# 4_TTL.net
KiCad netlist of a schematic drawn in EAGLE
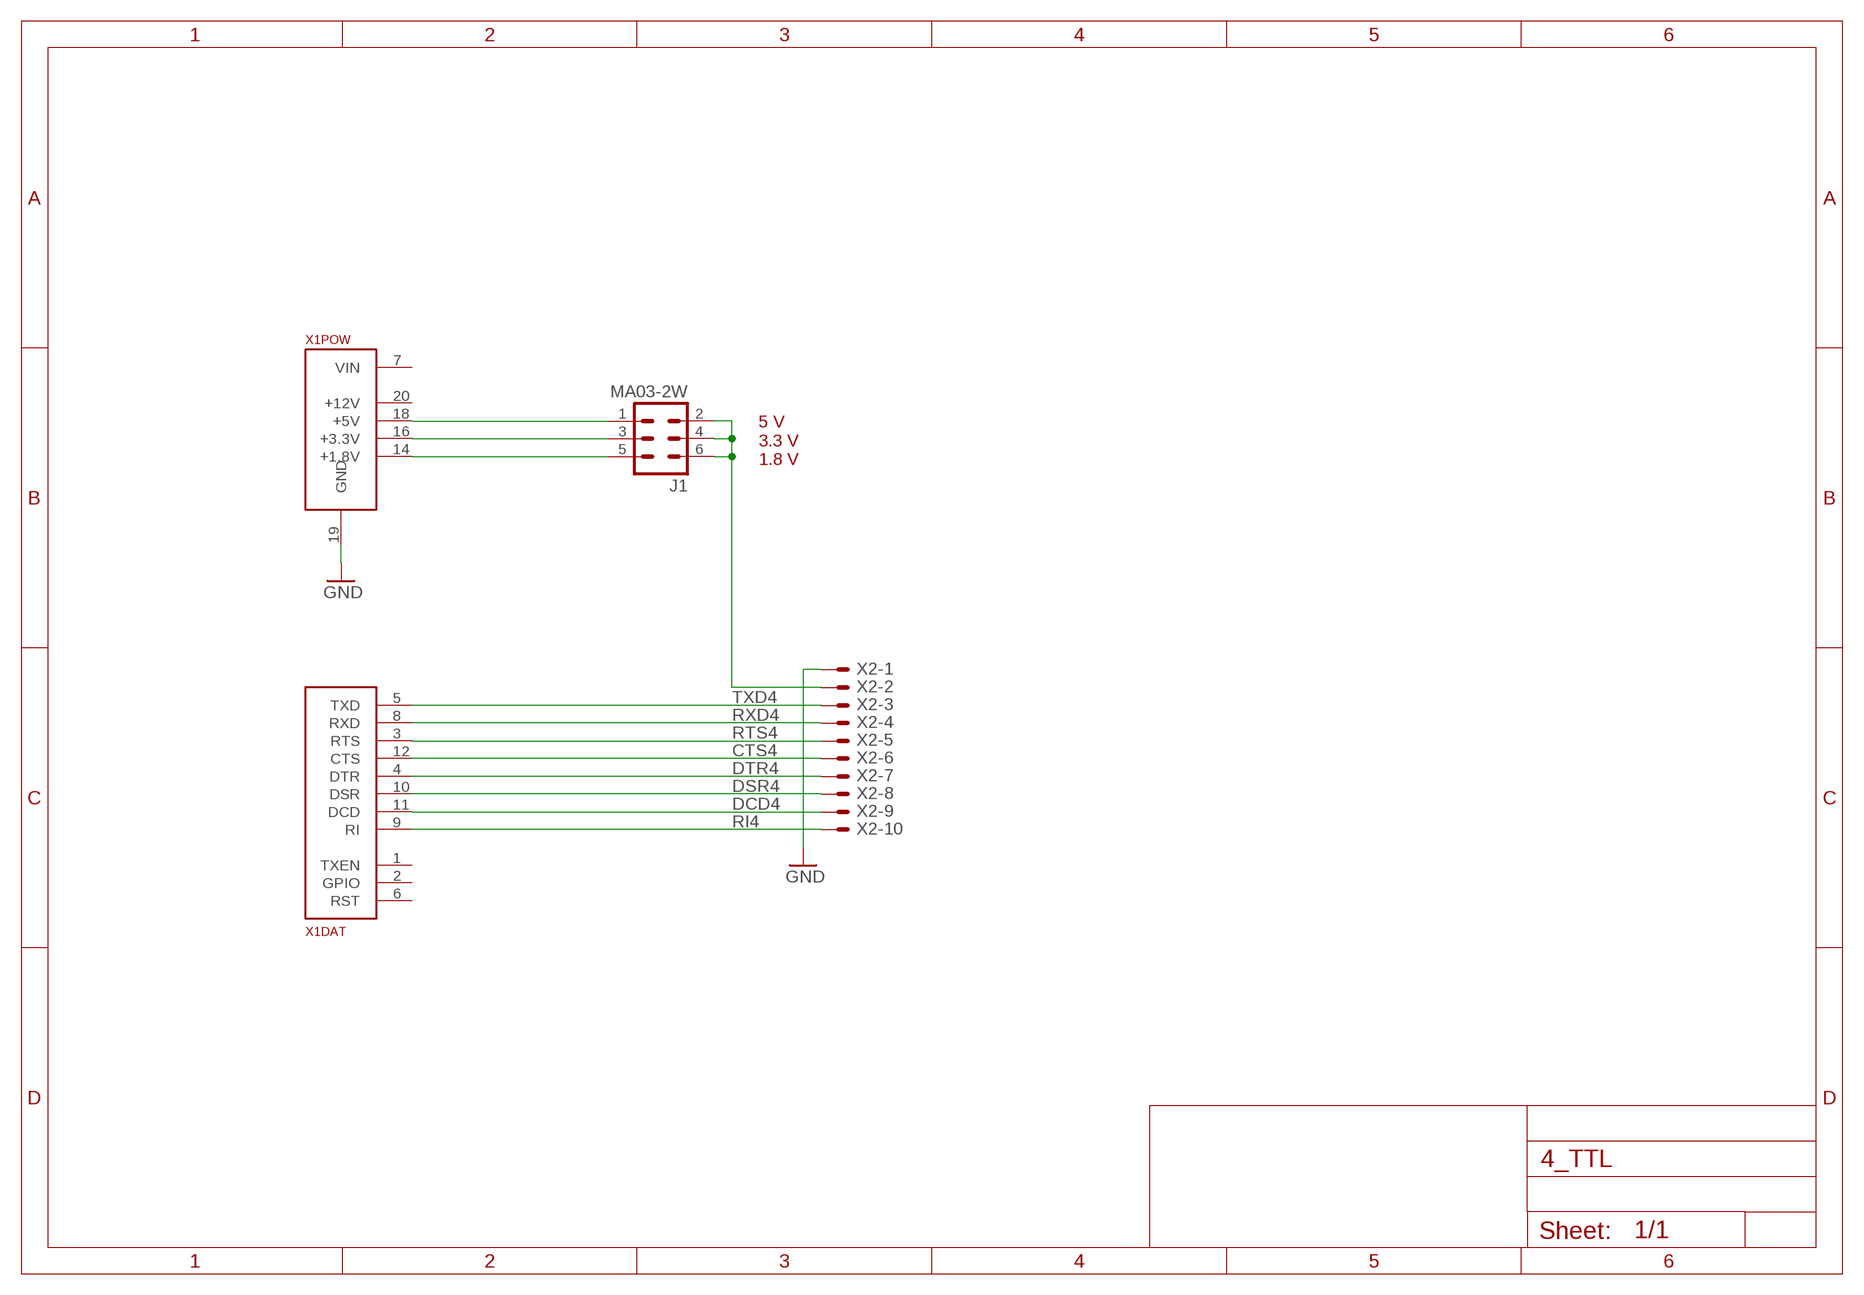
[diagram p0: schematic, sheet 1]

(export (version "E")
  (design (tool "Eeschema 10.0.6"))
  (components
    (comp (ref "J1")
      (value "MA03-2W")
      (footprint "eagle-import:MA03-2W")
      (libsource (lib "eagle-import") (part "MA03-2W"))
    )
    (comp (ref "X1")
      (value "ALLSERIALD")
      (footprint "eagle-import:DAUGHTER-THT")
      (libsource (lib "eagle-import") (part "ALLSERIALD"))
    )
    (comp (ref "X2")
      (value "AKL18X-10W")
      (footprint "eagle-import:AKL182-10")
      (libsource (lib "eagle-import") (part "AKL18X-10W"))
    )
  )
  (nets
    (net (code "1") (name "/CTS4") (class "Default")
      (node (ref "X1") (pin "12") (pinfunction "CTS_12") (pintype "bidirectional"))
      (node (ref "X2") (pin "P$6") (pinfunction "S_P$6") (pintype "passive"))
    )
    (net (code "2") (name "/DCD4") (class "Default")
      (node (ref "X1") (pin "11") (pinfunction "DCD_11") (pintype "bidirectional"))
      (node (ref "X2") (pin "P$9") (pinfunction "S_P$9") (pintype "passive"))
    )
    (net (code "3") (name "/DSR4") (class "Default")
      (node (ref "X1") (pin "10") (pinfunction "DSR_10") (pintype "bidirectional"))
      (node (ref "X2") (pin "P$8") (pinfunction "S_P$8") (pintype "passive"))
    )
    (net (code "4") (name "/DTR4") (class "Default")
      (node (ref "X1") (pin "4") (pinfunction "DTR_4") (pintype "bidirectional"))
      (node (ref "X2") (pin "P$7") (pinfunction "S_P$7") (pintype "passive"))
    )
    (net (code "5") (name "/RI4") (class "Default")
      (node (ref "X1") (pin "9") (pinfunction "RI_9") (pintype "bidirectional"))
      (node (ref "X2") (pin "P$10") (pinfunction "S_P$10") (pintype "passive"))
    )
    (net (code "6") (name "/RTS4") (class "Default")
      (node (ref "X1") (pin "3") (pinfunction "RTS_3") (pintype "bidirectional"))
      (node (ref "X2") (pin "P$5") (pinfunction "S_P$5") (pintype "passive"))
    )
    (net (code "7") (name "/RXD4") (class "Default")
      (node (ref "X1") (pin "8") (pinfunction "RXD_8") (pintype "bidirectional"))
      (node (ref "X2") (pin "P$4") (pinfunction "S_P$4") (pintype "passive"))
    )
    (net (code "8") (name "/TXD4") (class "Default")
      (node (ref "X1") (pin "5") (pinfunction "TXD_5") (pintype "bidirectional"))
      (node (ref "X2") (pin "P$3") (pinfunction "S_P$3") (pintype "passive"))
    )
    (net (code "9") (name "GND") (class "Default")
      (node (ref "X1") (pin "19") (pinfunction "GND_19") (pintype "bidirectional"))
      (node (ref "X2") (pin "P$1") (pinfunction "S_P$1") (pintype "passive"))
    )
    (net (code "10") (name "Net-(X1B-+1.8V)") (class "Default")
      (node (ref "J1") (pin "5") (pinfunction "5_5") (pintype "passive"))
      (node (ref "X1") (pin "14") (pinfunction "+1.8V_14") (pintype "bidirectional"))
    )
    (net (code "11") (name "Net-(X1B-+3.3V)") (class "Default")
      (node (ref "J1") (pin "3") (pinfunction "3_3") (pintype "passive"))
      (node (ref "X1") (pin "16") (pinfunction "+3.3V_16") (pintype "bidirectional"))
    )
    (net (code "12") (name "Net-(X1B-+5V)") (class "Default")
      (node (ref "J1") (pin "1") (pinfunction "1_1") (pintype "passive"))
      (node (ref "X1") (pin "18") (pinfunction "+5V_18") (pintype "bidirectional"))
    )
    (net (code "13") (name "Net-(X2C-S)") (class "Default")
      (node (ref "J1") (pin "2") (pinfunction "2_2") (pintype "passive"))
      (node (ref "J1") (pin "4") (pinfunction "4_4") (pintype "passive"))
      (node (ref "J1") (pin "6") (pinfunction "6_6") (pintype "passive"))
      (node (ref "X2") (pin "P$2") (pinfunction "S_P$2") (pintype "passive"))
    )
    (net (code "14") (name "unconnected-(X1A-GPIO-Pad2)") (class "Default")
      (node (ref "X1") (pin "2") (pinfunction "GPIO_2") (pintype "bidirectional"))
    )
    (net (code "15") (name "unconnected-(X1A-RST-Pad6)") (class "Default")
      (node (ref "X1") (pin "6") (pinfunction "RST_6") (pintype "bidirectional"))
    )
    (net (code "16") (name "unconnected-(X1A-TXEN-Pad1)") (class "Default")
      (node (ref "X1") (pin "1") (pinfunction "TXEN_1") (pintype "bidirectional"))
    )
    (net (code "17") (name "unconnected-(X1B-+12V-Pad20)") (class "Default")
      (node (ref "X1") (pin "20") (pinfunction "+12V_20") (pintype "bidirectional"))
    )
    (net (code "18") (name "unconnected-(X1B-VIN-Pad7)") (class "Default")
      (node (ref "X1") (pin "7") (pinfunction "VIN_7") (pintype "bidirectional"))
    )
  )
)
